# Adafruit_Bluefruit_LE_UART_Friend.net
KiCad netlist of a schematic drawn in EAGLE
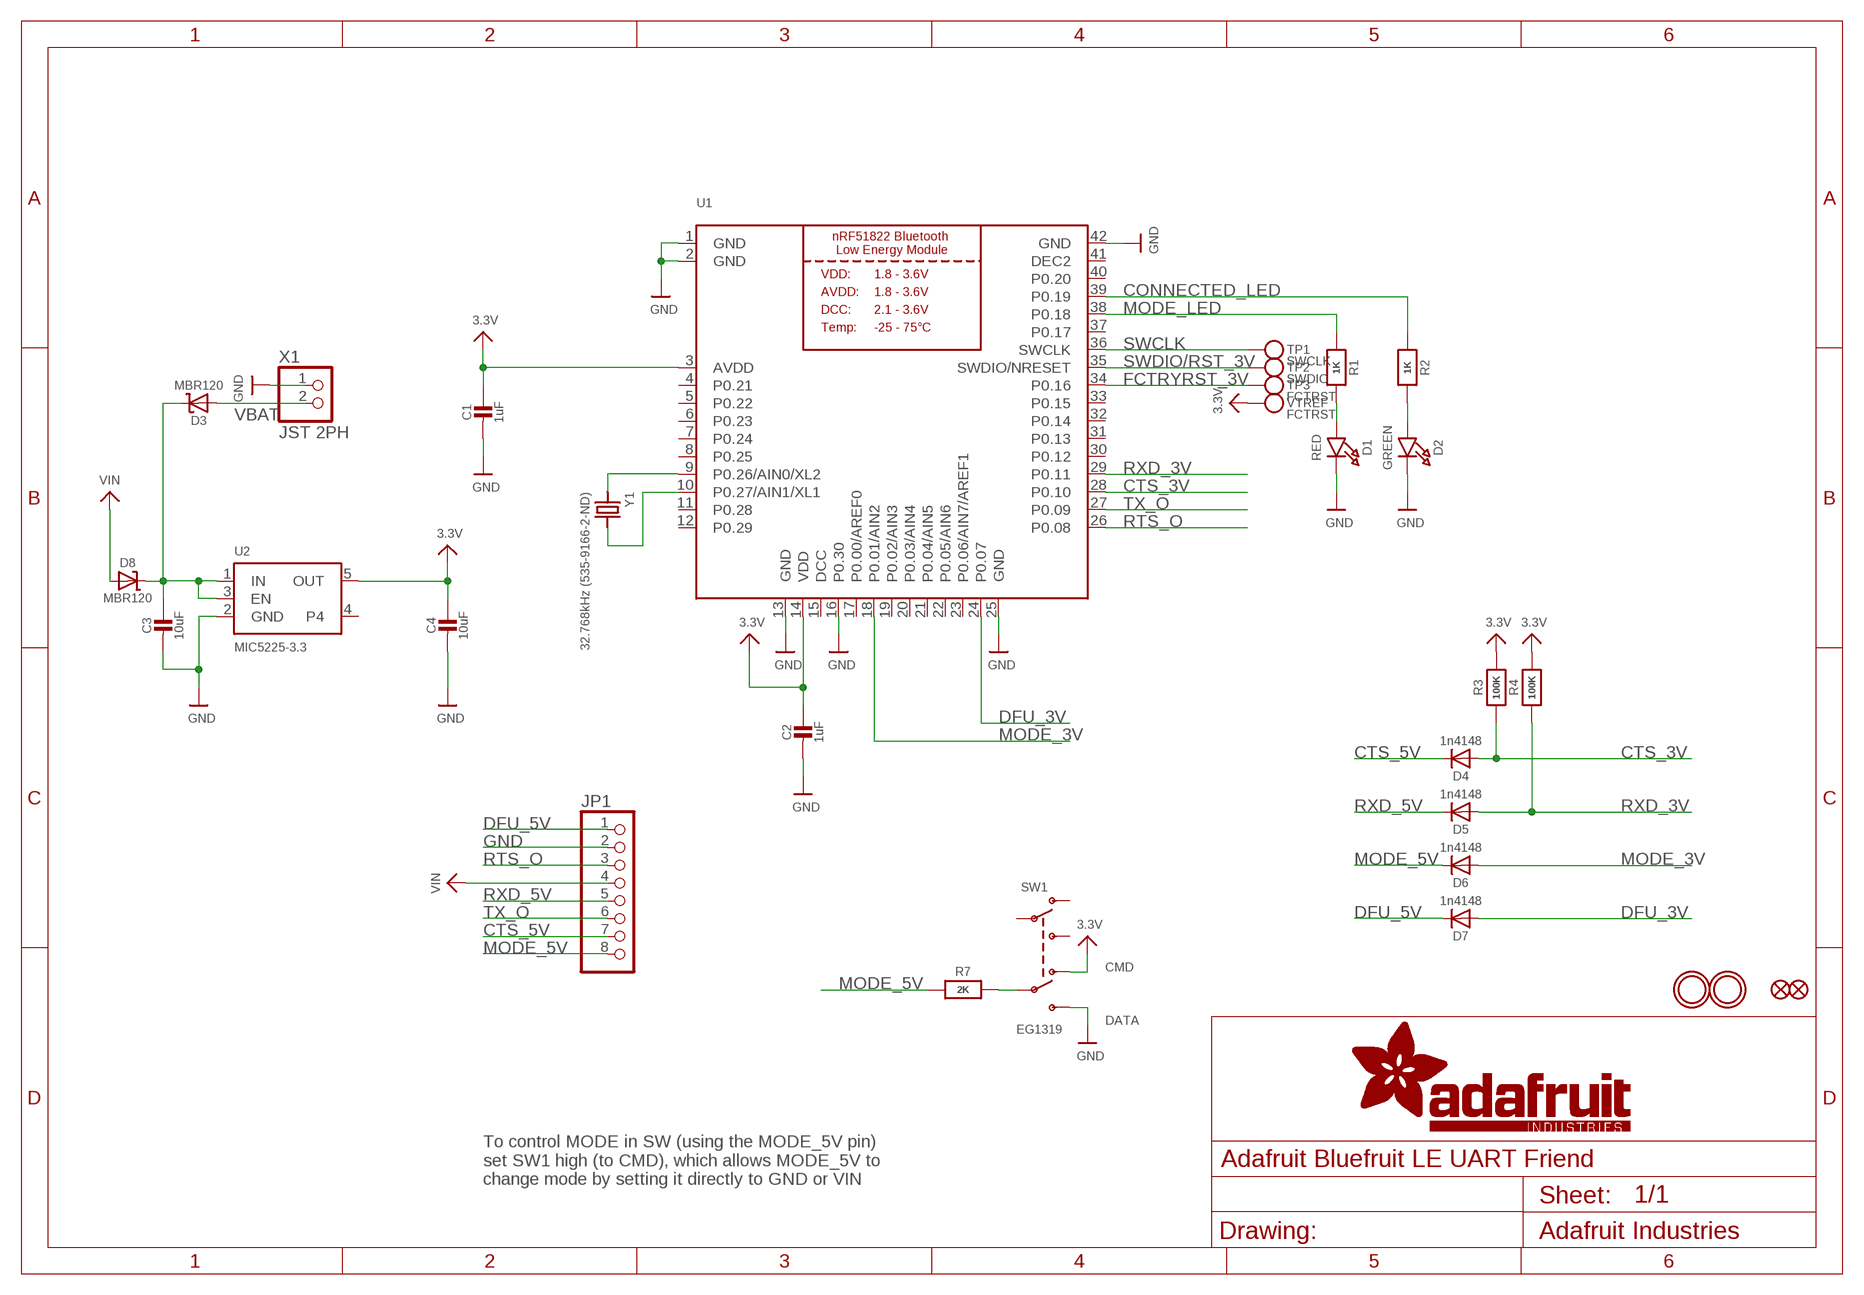
[diagram p0: schematic, sheet 1]

(export (version "E")
  (design (tool "Eeschema 10.0.6"))
  (components
    (comp (ref "C1")
      (value "1uF")
      (footprint "eagle-import:0805-NO")
      (libsource (lib "eagle-import") (part "CAP_CERAMIC0805-NOOUTLINE"))
    )
    (comp (ref "C2")
      (value "1uF")
      (footprint "eagle-import:0805-NO")
      (libsource (lib "eagle-import") (part "CAP_CERAMIC0805-NOOUTLINE"))
    )
    (comp (ref "C3")
      (value "10uF")
      (footprint "eagle-import:0805-NO")
      (libsource (lib "eagle-import") (part "CAP_CERAMIC0805-NOOUTLINE"))
    )
    (comp (ref "C4")
      (value "10uF")
      (footprint "eagle-import:0805-NO")
      (libsource (lib "eagle-import") (part "CAP_CERAMIC0805-NOOUTLINE"))
    )
    (comp (ref "D1")
      (value "RED")
      (footprint "eagle-import:CHIPLED_0805_NOOUTLINE")
      (libsource (lib "eagle-import") (part "LED0805_NOOUTLINE"))
    )
    (comp (ref "D2")
      (value "GREEN")
      (footprint "eagle-import:CHIPLED_0805_NOOUTLINE")
      (libsource (lib "eagle-import") (part "LED0805_NOOUTLINE"))
    )
    (comp (ref "D3")
      (value "MBR120")
      (footprint "eagle-import:SOD-123")
      (libsource (lib "eagle-import") (part "DIODE-SCHOTTKYSOD-123"))
    )
    (comp (ref "D4")
      (value "1n4148")
      (footprint "eagle-import:SOD-323")
      (libsource (lib "eagle-import") (part "DIODESOD-323"))
    )
    (comp (ref "D5")
      (value "1n4148")
      (footprint "eagle-import:SOD-323")
      (libsource (lib "eagle-import") (part "DIODESOD-323"))
    )
    (comp (ref "D6")
      (value "1n4148")
      (footprint "eagle-import:SOD-323")
      (libsource (lib "eagle-import") (part "DIODESOD-323"))
    )
    (comp (ref "D7")
      (value "1n4148")
      (footprint "eagle-import:SOD-323")
      (libsource (lib "eagle-import") (part "DIODESOD-323"))
    )
    (comp (ref "D8")
      (value "MBR120")
      (footprint "eagle-import:SOD-123")
      (libsource (lib "eagle-import") (part "DIODE-SCHOTTKYSOD-123"))
    )
    (comp (ref "FID1")
      (value "FIDUCIAL\"\"")
      (footprint "eagle-import:FIDUCIAL_1MM")
      (libsource (lib "eagle-import") (part "FIDUCIAL{dblquote}{dblquote}"))
    )
    (comp (ref "FID2")
      (value "FIDUCIAL\"\"")
      (footprint "eagle-import:FIDUCIAL_1MM")
      (libsource (lib "eagle-import") (part "FIDUCIAL{dblquote}{dblquote}"))
    )
    (comp (ref "JP1")
      (value "HEADER-1X876MIL")
      (footprint "eagle-import:1X08_ROUND_76")
      (libsource (lib "eagle-import") (part "HEADER-1X876MIL"))
    )
    (comp (ref "R1")
      (value "1K")
      (footprint "eagle-import:0805-NO")
      (libsource (lib "eagle-import") (part "RESISTOR0805_NOOUTLINE"))
    )
    (comp (ref "R2")
      (value "1K")
      (footprint "eagle-import:0805-NO")
      (libsource (lib "eagle-import") (part "RESISTOR0805_NOOUTLINE"))
    )
    (comp (ref "R3")
      (value "100K")
      (footprint "eagle-import:0805-NO")
      (libsource (lib "eagle-import") (part "RESISTOR0805_NOOUTLINE"))
    )
    (comp (ref "R4")
      (value "100K")
      (footprint "eagle-import:0805-NO")
      (libsource (lib "eagle-import") (part "RESISTOR0805_NOOUTLINE"))
    )
    (comp (ref "R7")
      (value "2K")
      (footprint "eagle-import:0805-NO")
      (libsource (lib "eagle-import") (part "RESISTOR0805_NOOUTLINE"))
    )
    (comp (ref "SW1")
      (value "EG1319")
      (footprint "eagle-import:EG1390")
      (libsource (lib "eagle-import") (part "SWITCH_DPDTEG1390"))
    )
    (comp (ref "TP1")
      (value "SWCLK")
      (footprint "eagle-import:PAD-1.5X2.0")
      (libsource (lib "eagle-import") (part "TESTPOINT1.5X2.0MM_NOCREAM"))
    )
    (comp (ref "TP2")
      (value "SWDIO")
      (footprint "eagle-import:PAD-1.5X2.0")
      (libsource (lib "eagle-import") (part "TESTPOINT1.5X2.0MM_NOCREAM"))
    )
    (comp (ref "TP3")
      (value "FCTRST")
      (footprint "eagle-import:PAD-1.5X2.0")
      (libsource (lib "eagle-import") (part "TESTPOINT1.5X2.0MM_NOCREAM"))
    )
    (comp (ref "U$28")
      (value "MOUNTINGHOLE2.5")
      (footprint "eagle-import:MOUNTINGHOLE_2.5_PLATED")
      (libsource (lib "eagle-import") (part "MOUNTINGHOLE2.5"))
    )
    (comp (ref "U$29")
      (value "MOUNTINGHOLE2.5")
      (footprint "eagle-import:MOUNTINGHOLE_2.5_PLATED")
      (libsource (lib "eagle-import") (part "MOUNTINGHOLE2.5"))
    )
    (comp (ref "U1")
      (value "NRF51822_MODULE_MDBT40")
      (footprint "eagle-import:BLE_MODULE_RAYTAC_MDBT40")
      (libsource (lib "eagle-import") (part "NRF51822_MODULE_MDBT40"))
    )
    (comp (ref "U2")
      (value "MIC5225-3.3")
      (footprint "eagle-import:SOT23-5")
      (libsource (lib "eagle-import") (part "VREG_SOT23-5"))
    )
    (comp (ref "VTREF")
      (value "FCTRST")
      (footprint "eagle-import:PAD-1.5X2.0")
      (libsource (lib "eagle-import") (part "TESTPOINT1.5X2.0MM_NOCREAM"))
    )
    (comp (ref "X1")
      (value "JST 2PH")
      (footprint "eagle-import:JSTPH2")
      (libsource (lib "eagle-import") (part "CON_JST_PH_2PIN"))
    )
    (comp (ref "Y1")
      (value "32.768kHz (535-9166-2-ND)")
      (footprint "eagle-import:CRYSTAL_CYL_2X6MM_SMT")
      (libsource (lib "eagle-import") (part "CRYSTAL2.0X6.0_32.768"))
    )
  )
  (nets
    (net (code "1") (name "/CONNECTED_LED") (class "Default")
      (node (ref "R2") (pin "1") (pinfunction "1_1") (pintype "passive"))
      (node (ref "U1") (pin "39") (pinfunction "P0.19_39") (pintype "bidirectional"))
    )
    (net (code "2") (name "/CTS_3V") (class "Default")
      (node (ref "D4") (pin "A") (pinfunction "A_A") (pintype "passive"))
      (node (ref "R3") (pin "1") (pinfunction "1_1") (pintype "passive"))
      (node (ref "U1") (pin "28") (pinfunction "P0.10_28") (pintype "bidirectional"))
    )
    (net (code "3") (name "/CTS_5V") (class "Default")
      (node (ref "D4") (pin "C") (pinfunction "C_C") (pintype "passive"))
      (node (ref "JP1") (pin "7") (pinfunction "7_7") (pintype "passive"))
    )
    (net (code "4") (name "/DCC") (class "Default")
      (node (ref "U1") (pin "15") (pinfunction "DCC_15") (pintype "power_in"))
    )
    (net (code "5") (name "/DEC2") (class "Default")
      (node (ref "U1") (pin "41") (pinfunction "DEC2_41") (pintype "power_in"))
    )
    (net (code "6") (name "/DFU_3V") (class "Default")
      (node (ref "D7") (pin "A") (pinfunction "A_A") (pintype "passive"))
      (node (ref "U1") (pin "24") (pinfunction "P0.07_24") (pintype "bidirectional"))
    )
    (net (code "7") (name "/DFU_5V") (class "Default")
      (node (ref "D7") (pin "C") (pinfunction "C_C") (pintype "passive"))
      (node (ref "JP1") (pin "1") (pinfunction "1_1") (pintype "passive"))
    )
    (net (code "8") (name "/FCTRYRST_3V") (class "Default")
      (node (ref "TP3") (pin "P$1") (pinfunction "P$1_P$1") (pintype "bidirectional"))
      (node (ref "U1") (pin "34") (pinfunction "P0.16_34") (pintype "bidirectional"))
    )
    (net (code "9") (name "/MODE_3V") (class "Default")
      (node (ref "D6") (pin "A") (pinfunction "A_A") (pintype "passive"))
      (node (ref "U1") (pin "18") (pinfunction "P0.01/AIN2_18") (pintype "bidirectional"))
    )
    (net (code "10") (name "/MODE_5V") (class "Default")
      (node (ref "D6") (pin "C") (pinfunction "C_C") (pintype "passive"))
      (node (ref "JP1") (pin "8") (pinfunction "8_8") (pintype "passive"))
      (node (ref "R7") (pin "1") (pinfunction "1_1") (pintype "passive"))
    )
    (net (code "11") (name "/MODE_LED") (class "Default")
      (node (ref "R1") (pin "1") (pinfunction "1_1") (pintype "passive"))
      (node (ref "U1") (pin "38") (pinfunction "P0.18_38") (pintype "bidirectional"))
    )
    (net (code "12") (name "/RTS_O") (class "Default")
      (node (ref "JP1") (pin "3") (pinfunction "3_3") (pintype "passive"))
      (node (ref "U1") (pin "26") (pinfunction "P0.08_26") (pintype "bidirectional"))
    )
    (net (code "13") (name "/RXD_3V") (class "Default")
      (node (ref "D5") (pin "A") (pinfunction "A_A") (pintype "passive"))
      (node (ref "R4") (pin "1") (pinfunction "1_1") (pintype "passive"))
      (node (ref "U1") (pin "29") (pinfunction "P0.11_29") (pintype "bidirectional"))
    )
    (net (code "14") (name "/RXD_5V") (class "Default")
      (node (ref "D5") (pin "C") (pinfunction "C_C") (pintype "passive"))
      (node (ref "JP1") (pin "5") (pinfunction "5_5") (pintype "passive"))
    )
    (net (code "15") (name "/SWCLK") (class "Default")
      (node (ref "TP1") (pin "P$1") (pinfunction "P$1_P$1") (pintype "bidirectional"))
      (node (ref "U1") (pin "36") (pinfunction "SWCLK_36") (pintype "bidirectional"))
    )
    (net (code "16") (name "/SWDIO{slash}RST_3V") (class "Default")
      (node (ref "TP2") (pin "P$1") (pinfunction "P$1_P$1") (pintype "bidirectional"))
      (node (ref "U1") (pin "35") (pinfunction "SWDIO/NRESET_35") (pintype "bidirectional"))
    )
    (net (code "17") (name "/TX_O") (class "Default")
      (node (ref "JP1") (pin "6") (pinfunction "6_6") (pintype "passive"))
      (node (ref "U1") (pin "27") (pinfunction "P0.09_27") (pintype "bidirectional"))
    )
    (net (code "18") (name "/VBAT") (class "Default")
      (node (ref "D3") (pin "A") (pinfunction "A_A") (pintype "passive"))
      (node (ref "X1") (pin "2") (pinfunction "2_2") (pintype "passive"))
    )
    (net (code "19") (name "3.3V") (class "Default")
      (node (ref "C1") (pin "1") (pinfunction "1_1") (pintype "passive"))
      (node (ref "C2") (pin "1") (pinfunction "1_1") (pintype "passive"))
      (node (ref "C4") (pin "1") (pinfunction "1_1") (pintype "passive"))
      (node (ref "R3") (pin "2") (pinfunction "2_2") (pintype "passive"))
      (node (ref "R4") (pin "2") (pinfunction "2_2") (pintype "passive"))
      (node (ref "SW1") (pin "O2") (pinfunction "O2_O2") (pintype "passive"))
      (node (ref "U1") (pin "14") (pinfunction "VDD_14") (pintype "power_in"))
      (node (ref "U1") (pin "3") (pinfunction "AVDD_3") (pintype "power_in"))
      (node (ref "U2") (pin "5") (pinfunction "OUT_5") (pintype "power_in"))
      (node (ref "VTREF") (pin "P$1") (pinfunction "P$1_P$1") (pintype "bidirectional"))
    )
    (net (code "20") (name "GND") (class "Default")
      (node (ref "C1") (pin "2") (pinfunction "2_2") (pintype "passive"))
      (node (ref "C2") (pin "2") (pinfunction "2_2") (pintype "passive"))
      (node (ref "C3") (pin "2") (pinfunction "2_2") (pintype "passive"))
      (node (ref "C4") (pin "2") (pinfunction "2_2") (pintype "passive"))
      (node (ref "D1") (pin "C") (pinfunction "C_C") (pintype "passive"))
      (node (ref "D2") (pin "C") (pinfunction "C_C") (pintype "passive"))
      (node (ref "JP1") (pin "2") (pinfunction "2_2") (pintype "passive"))
      (node (ref "SW1") (pin "S2") (pinfunction "S2_S2") (pintype "passive"))
      (node (ref "U1") (pin "1") (pinfunction "GND_1") (pintype "power_in"))
      (node (ref "U1") (pin "13") (pinfunction "GND_13") (pintype "power_in"))
      (node (ref "U1") (pin "16") (pinfunction "P0.30_16") (pintype "bidirectional"))
      (node (ref "U1") (pin "2") (pinfunction "GND_2") (pintype "power_in"))
      (node (ref "U1") (pin "25") (pinfunction "GND_25") (pintype "power_in"))
      (node (ref "U1") (pin "42") (pinfunction "GND_42") (pintype "power_in"))
      (node (ref "U2") (pin "2") (pinfunction "GND_2") (pintype "power_in"))
      (node (ref "X1") (pin "1") (pinfunction "1_1") (pintype "passive"))
    )
    (net (code "21") (name "Net-(D1-PadA)") (class "Default")
      (node (ref "D1") (pin "A") (pinfunction "A_A") (pintype "passive"))
      (node (ref "R1") (pin "2") (pinfunction "2_2") (pintype "passive"))
    )
    (net (code "22") (name "Net-(D2-PadA)") (class "Default")
      (node (ref "D2") (pin "A") (pinfunction "A_A") (pintype "passive"))
      (node (ref "R2") (pin "2") (pinfunction "2_2") (pintype "passive"))
    )
    (net (code "23") (name "Net-(R7-Pad2)") (class "Default")
      (node (ref "R7") (pin "2") (pinfunction "2_2") (pintype "passive"))
      (node (ref "SW1") (pin "P2") (pinfunction "P2_P2") (pintype "passive"))
    )
    (net (code "24") (name "Net-(U1-P0.26{slash}AIN0{slash}XL2)") (class "Default")
      (node (ref "U1") (pin "9") (pinfunction "P0.26/AIN0/XL2_9") (pintype "bidirectional"))
      (node (ref "Y1") (pin "1") (pinfunction "1_1") (pintype "passive"))
    )
    (net (code "25") (name "Net-(U1-P0.27{slash}AIN1{slash}XL1)") (class "Default")
      (node (ref "U1") (pin "10") (pinfunction "P0.27/AIN1/XL1_10") (pintype "bidirectional"))
      (node (ref "Y1") (pin "2") (pinfunction "2_2") (pintype "passive"))
    )
    (net (code "26") (name "Net-(U2-EN)") (class "Default")
      (node (ref "C3") (pin "1") (pinfunction "1_1") (pintype "passive"))
      (node (ref "D3") (pin "C") (pinfunction "C_C") (pintype "passive"))
      (node (ref "D8") (pin "C") (pinfunction "C_C") (pintype "passive"))
      (node (ref "U2") (pin "1") (pinfunction "IN_1") (pintype "power_in"))
      (node (ref "U2") (pin "3") (pinfunction "EN_3") (pintype "input"))
    )
    (net (code "27") (name "VIN") (class "Default")
      (node (ref "D8") (pin "A") (pinfunction "A_A") (pintype "passive"))
      (node (ref "JP1") (pin "4") (pinfunction "4_4") (pintype "passive"))
    )
    (net (code "28") (name "unconnected-(SW1-PadO1)") (class "Default")
      (node (ref "SW1") (pin "O1") (pinfunction "O1_O1") (pintype "passive"))
    )
    (net (code "29") (name "unconnected-(SW1-PadP1)") (class "Default")
      (node (ref "SW1") (pin "P1") (pinfunction "P1_P1") (pintype "passive"))
    )
    (net (code "30") (name "unconnected-(SW1-PadS1)") (class "Default")
      (node (ref "SW1") (pin "S1") (pinfunction "S1_S1") (pintype "passive"))
    )
    (net (code "31") (name "unconnected-(U1-P0.00{slash}AREF0-Pad17)") (class "Default")
      (node (ref "U1") (pin "17") (pinfunction "P0.00/AREF0_17") (pintype "bidirectional"))
    )
    (net (code "32") (name "unconnected-(U1-P0.02{slash}AIN3-Pad19)") (class "Default")
      (node (ref "U1") (pin "19") (pinfunction "P0.02/AIN3_19") (pintype "bidirectional"))
    )
    (net (code "33") (name "unconnected-(U1-P0.03{slash}AIN4-Pad20)") (class "Default")
      (node (ref "U1") (pin "20") (pinfunction "P0.03/AIN4_20") (pintype "bidirectional"))
    )
    (net (code "34") (name "unconnected-(U1-P0.04{slash}AIN5-Pad21)") (class "Default")
      (node (ref "U1") (pin "21") (pinfunction "P0.04/AIN5_21") (pintype "bidirectional"))
    )
    (net (code "35") (name "unconnected-(U1-P0.05{slash}AIN6-Pad22)") (class "Default")
      (node (ref "U1") (pin "22") (pinfunction "P0.05/AIN6_22") (pintype "bidirectional"))
    )
    (net (code "36") (name "unconnected-(U1-P0.06{slash}AIN7{slash}AREF1-Pad23)") (class "Default")
      (node (ref "U1") (pin "23") (pinfunction "P0.06/AIN7/AREF1_23") (pintype "bidirectional"))
    )
    (net (code "37") (name "unconnected-(U1-P0.12-Pad30)") (class "Default")
      (node (ref "U1") (pin "30") (pinfunction "P0.12_30") (pintype "bidirectional"))
    )
    (net (code "38") (name "unconnected-(U1-P0.13-Pad31)") (class "Default")
      (node (ref "U1") (pin "31") (pinfunction "P0.13_31") (pintype "bidirectional"))
    )
    (net (code "39") (name "unconnected-(U1-P0.14-Pad32)") (class "Default")
      (node (ref "U1") (pin "32") (pinfunction "P0.14_32") (pintype "bidirectional"))
    )
    (net (code "40") (name "unconnected-(U1-P0.15-Pad33)") (class "Default")
      (node (ref "U1") (pin "33") (pinfunction "P0.15_33") (pintype "bidirectional"))
    )
    (net (code "41") (name "unconnected-(U1-P0.17-Pad37)") (class "Default")
      (node (ref "U1") (pin "37") (pinfunction "P0.17_37") (pintype "bidirectional"))
    )
    (net (code "42") (name "unconnected-(U1-P0.20-Pad40)") (class "Default")
      (node (ref "U1") (pin "40") (pinfunction "P0.20_40") (pintype "bidirectional"))
    )
    (net (code "43") (name "unconnected-(U1-P0.21-Pad4)") (class "Default")
      (node (ref "U1") (pin "4") (pinfunction "P0.21_4") (pintype "bidirectional"))
    )
    (net (code "44") (name "unconnected-(U1-P0.22-Pad5)") (class "Default")
      (node (ref "U1") (pin "5") (pinfunction "P0.22_5") (pintype "bidirectional"))
    )
    (net (code "45") (name "unconnected-(U1-P0.23-Pad6)") (class "Default")
      (node (ref "U1") (pin "6") (pinfunction "P0.23_6") (pintype "bidirectional"))
    )
    (net (code "46") (name "unconnected-(U1-P0.24-Pad7)") (class "Default")
      (node (ref "U1") (pin "7") (pinfunction "P0.24_7") (pintype "bidirectional"))
    )
    (net (code "47") (name "unconnected-(U1-P0.25-Pad8)") (class "Default")
      (node (ref "U1") (pin "8") (pinfunction "P0.25_8") (pintype "bidirectional"))
    )
    (net (code "48") (name "unconnected-(U1-P0.28-Pad11)") (class "Default")
      (node (ref "U1") (pin "11") (pinfunction "P0.28_11") (pintype "bidirectional"))
    )
    (net (code "49") (name "unconnected-(U1-P0.29-Pad12)") (class "Default")
      (node (ref "U1") (pin "12") (pinfunction "P0.29_12") (pintype "bidirectional"))
    )
    (net (code "50") (name "unconnected-(U2-P4-Pad4)") (class "Default")
      (node (ref "U2") (pin "4") (pinfunction "P4_4") (pintype "bidirectional"))
    )
  )
)
